# ASBB_GiantGecko.net
KiCad netlist of a schematic drawn in Altium Designer
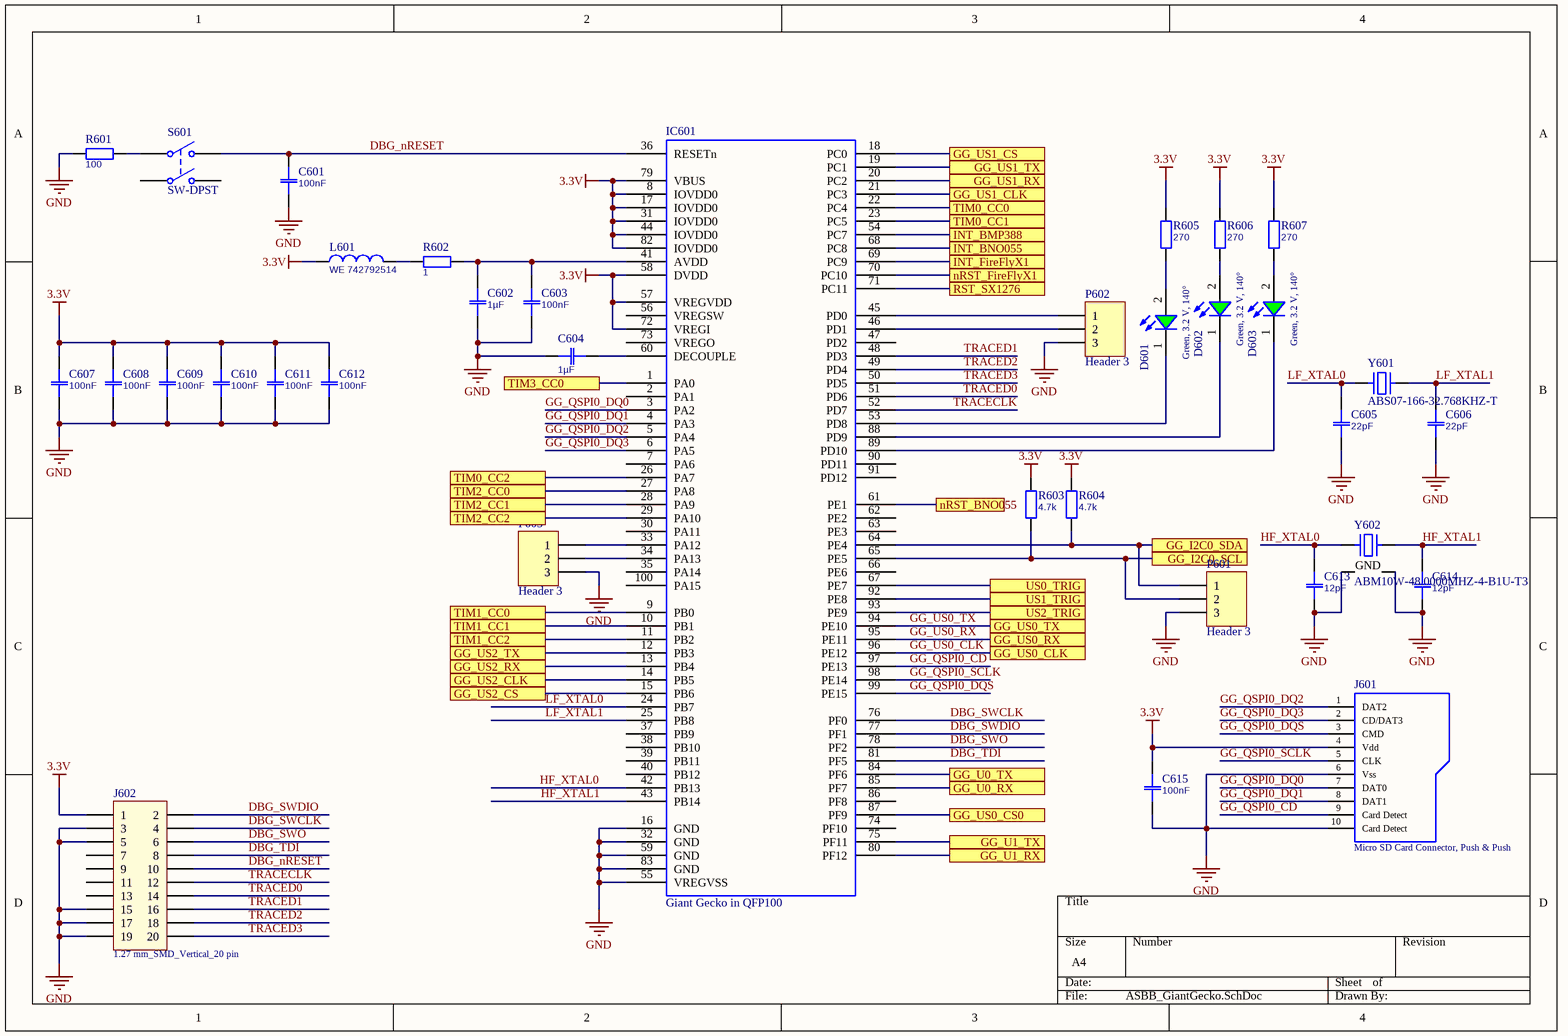
[diagram p0: ASBB_GiantGecko.SchDoc]

(export (version "E")
  (design (tool "Eeschema 10.0.6"))
  (components
    (comp (ref "C601")
      (value "100nF")
      (footprint "0603")
      (description "Capacitor")
      (fields (field (name "PARTNUMBER") "?"))
      (libsource (lib "FZI") (part "Capacitor"))
    )
    (comp (ref "C602")
      (value "1µF")
      (footprint "0603")
      (description "Capacitor")
      (fields (field (name "PARTNUMBER") "?"))
      (libsource (lib "FZI") (part "Capacitor"))
    )
    (comp (ref "C603")
      (value "100nF")
      (footprint "0603")
      (description "Capacitor")
      (fields (field (name "PARTNUMBER") "?"))
      (libsource (lib "FZI") (part "Capacitor"))
    )
    (comp (ref "C604")
      (value "1µF")
      (footprint "0603")
      (description "Capacitor")
      (fields (field (name "PARTNUMBER") "?"))
      (libsource (lib "FZI") (part "Capacitor"))
    )
    (comp (ref "C605")
      (value "22pF")
      (footprint "0603")
      (description "Capacitor")
      (fields (field (name "PARTNUMBER") "?"))
      (libsource (lib "FZI") (part "Capacitor"))
    )
    (comp (ref "C606")
      (value "22pF")
      (footprint "0603")
      (description "Capacitor")
      (fields (field (name "PARTNUMBER") "?"))
      (libsource (lib "FZI") (part "Capacitor"))
    )
    (comp (ref "C607")
      (value "100nF")
      (footprint "0603")
      (description "Capacitor")
      (fields (field (name "PARTNUMBER") "?"))
      (libsource (lib "FZI") (part "Capacitor"))
    )
    (comp (ref "C608")
      (value "100nF")
      (footprint "0603")
      (description "Capacitor")
      (fields (field (name "PARTNUMBER") "?"))
      (libsource (lib "FZI") (part "Capacitor"))
    )
    (comp (ref "C609")
      (value "100nF")
      (footprint "0603")
      (description "Capacitor")
      (fields (field (name "PARTNUMBER") "?"))
      (libsource (lib "FZI") (part "Capacitor"))
    )
    (comp (ref "C610")
      (value "100nF")
      (footprint "0603")
      (description "Capacitor")
      (fields (field (name "PARTNUMBER") "?"))
      (libsource (lib "FZI") (part "Capacitor"))
    )
    (comp (ref "C611")
      (value "100nF")
      (footprint "0603")
      (description "Capacitor")
      (fields (field (name "PARTNUMBER") "?"))
      (libsource (lib "FZI") (part "Capacitor"))
    )
    (comp (ref "C612")
      (value "100nF")
      (footprint "0603")
      (description "Capacitor")
      (fields (field (name "PARTNUMBER") "?"))
      (libsource (lib "FZI") (part "Capacitor"))
    )
    (comp (ref "C613")
      (value "12pF")
      (footprint "0603")
      (description "Capacitor")
      (fields (field (name "PARTNUMBER") "?"))
      (libsource (lib "FZI") (part "Capacitor"))
    )
    (comp (ref "C614")
      (value "12pF")
      (footprint "0603")
      (description "Capacitor")
      (fields (field (name "PARTNUMBER") "?"))
      (libsource (lib "FZI") (part "Capacitor"))
    )
    (comp (ref "C615")
      (value "100nF")
      (footprint "0603")
      (description "Capacitor")
      (fields (field (name "PARTNUMBER") "?"))
      (libsource (lib "FZI") (part "Capacitor"))
    )
    (comp (ref "D601")
      (value "Green, 3.2 V, 140°")
      (footprint "WL-SMCW_0603")
      (description "WL-SMCW SMD Mono-color Chip LED Waterclear, size 0603, Green, 3.2 V, 140°")
      (fields (field (name "PART NUMBER") "150060GS75000") (field (name "PUBLISHER") "Wurth Elektronik"))
      (libsource (lib "ALTIUM-WL-SMCW-rev18b") (part "150060GS75000"))
    )
    (comp (ref "D602")
      (value "Green, 3.2 V, 140°")
      (footprint "WL-SMCW_0603")
      (description "WL-SMCW SMD Mono-color Chip LED Waterclear, size 0603, Green, 3.2 V, 140°")
      (fields (field (name "PART NUMBER") "150060GS75000") (field (name "PUBLISHER") "Wurth Elektronik"))
      (libsource (lib "ALTIUM-WL-SMCW-rev18b") (part "150060GS75000"))
    )
    (comp (ref "D603")
      (value "Green, 3.2 V, 140°")
      (footprint "WL-SMCW_0603")
      (description "WL-SMCW SMD Mono-color Chip LED Waterclear, size 0603, Green, 3.2 V, 140°")
      (fields (field (name "PART NUMBER") "150060GS75000") (field (name "PUBLISHER") "Wurth Elektronik"))
      (libsource (lib "ALTIUM-WL-SMCW-rev18b") (part "150060GS75000"))
    )
    (comp (ref "IC601")
      (value "Giant Gecko in QFP100")
      (footprint "TQFP100")
      (libsource (lib "ASBB") (part "EFM32GG11B8xx"))
    )
    (comp (ref "J601")
      (value "Micro SD Card Connector, Push & Push")
      (footprint "693071010811")
      (description "WR-CRD Micro SD Card Connector, Push & Push, with card detection")
      (fields (field (name "PART NUMBER") "693071010811") (field (name "PUBLISHER") "Wurth Elektronik"))
      (libsource (lib "ALTIUM-WR-CRD-rev18a") (part "693071010811"))
    )
    (comp (ref "J602")
      (value "1.27 mm_SMD_Vertical_20 pin")
      (footprint "62102021021")
      (description "Pin Header WR-PHD, pitch 1.27 mm, SMD, Vertical, dual row, 20 pin")
      (fields (field (name "PART NUMBER") "62102021021") (field (name "PUBLISHER") "Wurth Elektronik"))
      (libsource (lib "6220xx21121 (rev18a)") (part "62102021021"))
    )
    (comp (ref "L601")
      (value "WE 742792514")
      (footprint "1812")
      (description "Inductor")
      (fields (field (name "PARTNUMBER") "?"))
      (libsource (lib "FZI") (part "Inductor"))
    )
    (comp (ref "P601")
      (value "Header 3")
      (footprint "HDR1X3")
      (description "Header, 3-Pin")
      (fields (field (name "PUBLISHER") "Altium Limited"))
      (libsource (lib "Miscellaneous Connectors") (part "Header 3"))
    )
    (comp (ref "P602")
      (value "Header 3")
      (footprint "HDR1X3")
      (description "Header, 3-Pin")
      (fields (field (name "PUBLISHER") "Altium Limited"))
      (libsource (lib "Miscellaneous Connectors") (part "Header 3"))
    )
    (comp (ref "P603")
      (value "Header 3")
      (footprint "HDR1X3")
      (description "Header, 3-Pin")
      (fields (field (name "PUBLISHER") "Altium Limited"))
      (libsource (lib "") (part "Header 3_1"))
    )
    (comp (ref "R601")
      (value "100")
      (footprint "0603")
      (description "Resistor")
      (fields (field (name "PARTNUMBER") "?"))
      (libsource (lib "FZI") (part "Resistor"))
    )
    (comp (ref "R602")
      (value "1")
      (footprint "0603")
      (description "Resistor")
      (fields (field (name "PARTNUMBER") "?"))
      (libsource (lib "FZI") (part "Resistor"))
    )
    (comp (ref "R603")
      (value "4.7k")
      (footprint "0603")
      (description "Resistor")
      (fields (field (name "PARTNUMBER") "?"))
      (libsource (lib "FZI") (part "Resistor"))
    )
    (comp (ref "R604")
      (value "4.7k")
      (footprint "0603")
      (description "Resistor")
      (fields (field (name "PARTNUMBER") "?"))
      (libsource (lib "FZI") (part "Resistor"))
    )
    (comp (ref "R605")
      (value "270")
      (footprint "0603")
      (description "Resistor")
      (fields (field (name "PARTNUMBER") "?"))
      (libsource (lib "FZI") (part "Resistor"))
    )
    (comp (ref "R606")
      (value "270")
      (footprint "0603")
      (description "Resistor")
      (fields (field (name "PARTNUMBER") "?"))
      (libsource (lib "FZI") (part "Resistor"))
    )
    (comp (ref "R607")
      (value "270")
      (footprint "0603")
      (description "Resistor")
      (fields (field (name "PARTNUMBER") "?"))
      (libsource (lib "FZI") (part "Resistor"))
    )
    (comp (ref "S601")
      (value "SW-DPST")
      (footprint "DPST-4")
      (description "Double-Pole, Single-Throw Switch")
      (fields (field (name "PUBLISHER") "Altium Limited"))
      (libsource (lib "Miscellaneous Devices") (part "SW-DPST"))
    )
    (comp (ref "Y601")
      (value "ABS07-166-32.768KHZ-T")
      (footprint "ABRACON ABS07")
      (description "SMT Crystal")
      (libsource (lib "Crystals") (part "Abracon Crystal ABS06"))
    )
    (comp (ref "Y602")
      (value "ABM10W-48.0000MHZ-4-B1U-T3")
      (footprint "ABRACON ABM10")
      (description "SMT Crystal")
      (libsource (lib "Crystals") (part "Abracon Crystal ABM10"))
    )
  )
  (nets
    (net (code "1") (name "/DBG_SWCLK") (class "Default")
      (node (ref "IC601") (pin "76") (pinfunction "PF0_76") (pintype "power_in"))
      (node (ref "J602") (pin "4") (pinfunction "4_4") (pintype "passive"))
    )
    (net (code "2") (name "/DBG_SWDIO") (class "Default")
      (node (ref "IC601") (pin "77") (pinfunction "PF1_77") (pintype "power_in"))
      (node (ref "J602") (pin "2") (pinfunction "2_2") (pintype "passive"))
    )
    (net (code "3") (name "/DBG_SWO") (class "Default")
      (node (ref "IC601") (pin "78") (pinfunction "PF2_78") (pintype "power_in"))
      (node (ref "J602") (pin "6") (pinfunction "6_6") (pintype "passive"))
    )
    (net (code "4") (name "/DBG_TDI") (class "Default")
      (node (ref "IC601") (pin "81") (pinfunction "PF5_81") (pintype "power_in"))
      (node (ref "J602") (pin "8") (pinfunction "8_8") (pintype "passive"))
    )
    (net (code "5") (name "/DBG_nRESET") (class "Default")
      (node (ref "C601") (pin "1") (pinfunction "1_1") (pintype "passive"))
      (node (ref "IC601") (pin "36") (pinfunction "RESETn_36") (pintype "power_in"))
      (node (ref "J602") (pin "10") (pinfunction "10_10") (pintype "passive"))
      (node (ref "S601") (pin "2") (pinfunction "NO1_2") (pintype "passive"))
    )
    (net (code "6") (name "/GG_I2C0_SCL") (class "Default")
      (node (ref "IC601") (pin "65") (pinfunction "PE5_65") (pintype "power_in"))
      (node (ref "P601") (pin "2") (pinfunction "2_2") (pintype "passive"))
      (node (ref "R603") (pin "1") (pinfunction "1_1") (pintype "passive"))
    )
    (net (code "7") (name "/GG_I2C0_SDA") (class "Default")
      (node (ref "IC601") (pin "64") (pinfunction "PE4_64") (pintype "power_in"))
      (node (ref "P601") (pin "1") (pinfunction "1_1") (pintype "passive"))
      (node (ref "R604") (pin "1") (pinfunction "1_1") (pintype "passive"))
    )
    (net (code "8") (name "/GG_QSPI0_CD") (class "Default")
      (node (ref "IC601") (pin "97") (pinfunction "PE13_97") (pintype "power_in"))
      (node (ref "J601") (pin "9") (pinfunction "Card_Detect_9") (pintype "passive"))
    )
    (net (code "9") (name "/GG_QSPI0_DQ0") (class "Default")
      (node (ref "IC601") (pin "3") (pinfunction "PA2_3") (pintype "power_in"))
      (node (ref "J601") (pin "7") (pinfunction "DAT0_7") (pintype "passive"))
    )
    (net (code "10") (name "/GG_QSPI0_DQ1") (class "Default")
      (node (ref "IC601") (pin "4") (pinfunction "PA3_4") (pintype "power_in"))
      (node (ref "J601") (pin "8") (pinfunction "DAT1_8") (pintype "passive"))
    )
    (net (code "11") (name "/GG_QSPI0_DQ2") (class "Default")
      (node (ref "IC601") (pin "5") (pinfunction "PA4_5") (pintype "power_in"))
      (node (ref "J601") (pin "1") (pinfunction "DAT2_1") (pintype "passive"))
    )
    (net (code "12") (name "/GG_QSPI0_DQ3") (class "Default")
      (node (ref "IC601") (pin "6") (pinfunction "PA5_6") (pintype "power_in"))
      (node (ref "J601") (pin "2") (pinfunction "CD/DAT3_2") (pintype "passive"))
    )
    (net (code "13") (name "/GG_QSPI0_DQS") (class "Default")
      (node (ref "IC601") (pin "99") (pinfunction "PE15_99") (pintype "power_in"))
      (node (ref "J601") (pin "3") (pinfunction "CMD_3") (pintype "passive"))
    )
    (net (code "14") (name "/GG_QSPI0_SCLK") (class "Default")
      (node (ref "IC601") (pin "98") (pinfunction "PE14_98") (pintype "power_in"))
      (node (ref "J601") (pin "5") (pinfunction "CLK_5") (pintype "passive"))
    )
    (net (code "15") (name "/GG_U0_RX") (class "Default")
      (node (ref "IC601") (pin "85") (pinfunction "PF7_85") (pintype "power_in"))
    )
    (net (code "16") (name "/GG_U0_TX") (class "Default")
      (node (ref "IC601") (pin "84") (pinfunction "PF6_84") (pintype "power_in"))
    )
    (net (code "17") (name "/GG_U1_RX") (class "Default")
      (node (ref "IC601") (pin "80") (pinfunction "PF12_80") (pintype "power_in"))
    )
    (net (code "18") (name "/GG_U1_TX") (class "Default")
      (node (ref "IC601") (pin "75") (pinfunction "PF11_75") (pintype "power_in"))
    )
    (net (code "19") (name "/GG_US0_CLK") (class "Default")
      (node (ref "IC601") (pin "96") (pinfunction "PE12_96") (pintype "power_in"))
    )
    (net (code "20") (name "/GG_US0_CS0") (class "Default")
      (node (ref "IC601") (pin "87") (pinfunction "PF9_87") (pintype "power_in"))
    )
    (net (code "21") (name "/GG_US0_RX") (class "Default")
      (node (ref "IC601") (pin "95") (pinfunction "PE11_95") (pintype "power_in"))
    )
    (net (code "22") (name "/GG_US0_TX") (class "Default")
      (node (ref "IC601") (pin "94") (pinfunction "PE10_94") (pintype "power_in"))
    )
    (net (code "23") (name "/GG_US1_CLK") (class "Default")
      (node (ref "IC601") (pin "21") (pinfunction "PC3_21") (pintype "power_in"))
    )
    (net (code "24") (name "/GG_US1_CS") (class "Default")
      (node (ref "IC601") (pin "18") (pinfunction "PC0_18") (pintype "power_in"))
    )
    (net (code "25") (name "/GG_US1_RX") (class "Default")
      (node (ref "IC601") (pin "20") (pinfunction "PC2_20") (pintype "power_in"))
    )
    (net (code "26") (name "/GG_US1_TX") (class "Default")
      (node (ref "IC601") (pin "19") (pinfunction "PC1_19") (pintype "power_in"))
    )
    (net (code "27") (name "/GG_US2_CLK") (class "Default")
      (node (ref "IC601") (pin "14") (pinfunction "PB5_14") (pintype "power_in"))
    )
    (net (code "28") (name "/GG_US2_CS") (class "Default")
      (node (ref "IC601") (pin "15") (pinfunction "PB6_15") (pintype "power_in"))
    )
    (net (code "29") (name "/GG_US2_RX") (class "Default")
      (node (ref "IC601") (pin "13") (pinfunction "PB4_13") (pintype "power_in"))
    )
    (net (code "30") (name "/GG_US2_TX") (class "Default")
      (node (ref "IC601") (pin "12") (pinfunction "PB3_12") (pintype "power_in"))
    )
    (net (code "31") (name "/HF_XTAL0") (class "Default")
      (node (ref "C613") (pin "1") (pinfunction "1_1") (pintype "passive"))
      (node (ref "IC601") (pin "42") (pinfunction "PB13_42") (pintype "power_in"))
      (node (ref "Y602") (pin "1") (pinfunction "1_1") (pintype "passive"))
    )
    (net (code "32") (name "/HF_XTAL1") (class "Default")
      (node (ref "C614") (pin "1") (pinfunction "1_1") (pintype "passive"))
      (node (ref "IC601") (pin "43") (pinfunction "PB14_43") (pintype "power_in"))
      (node (ref "Y602") (pin "3") (pinfunction "3_3") (pintype "passive"))
    )
    (net (code "33") (name "/INT_BMP388") (class "Default")
      (node (ref "IC601") (pin "54") (pinfunction "PC7_54") (pintype "power_in"))
    )
    (net (code "34") (name "/INT_BNO055") (class "Default")
      (node (ref "IC601") (pin "68") (pinfunction "PC8_68") (pintype "power_in"))
    )
    (net (code "35") (name "/INT_FireFlyX1") (class "Default")
      (node (ref "IC601") (pin "69") (pinfunction "PC9_69") (pintype "power_in"))
    )
    (net (code "36") (name "/LF_XTAL0") (class "Default")
      (node (ref "C605") (pin "1") (pinfunction "1_1") (pintype "passive"))
      (node (ref "IC601") (pin "24") (pinfunction "PB7_24") (pintype "power_in"))
      (node (ref "Y601") (pin "1") (pinfunction "1_1") (pintype "passive"))
    )
    (net (code "37") (name "/LF_XTAL1") (class "Default")
      (node (ref "C606") (pin "1") (pinfunction "1_1") (pintype "passive"))
      (node (ref "IC601") (pin "25") (pinfunction "PB8_25") (pintype "power_in"))
      (node (ref "Y601") (pin "2") (pinfunction "2_2") (pintype "passive"))
    )
    (net (code "38") (name "/RST_SX1276") (class "Default")
      (node (ref "IC601") (pin "71") (pinfunction "PC11_71") (pintype "power_in"))
    )
    (net (code "39") (name "/TIM0_CC0") (class "Default")
      (node (ref "IC601") (pin "22") (pinfunction "PC4_22") (pintype "power_in"))
    )
    (net (code "40") (name "/TIM0_CC1") (class "Default")
      (node (ref "IC601") (pin "23") (pinfunction "PC5_23") (pintype "power_in"))
    )
    (net (code "41") (name "/TIM0_CC2") (class "Default")
      (node (ref "IC601") (pin "26") (pinfunction "PA7_26") (pintype "power_in"))
    )
    (net (code "42") (name "/TIM1_CC0") (class "Default")
      (node (ref "IC601") (pin "9") (pinfunction "PB0_9") (pintype "power_in"))
    )
    (net (code "43") (name "/TIM1_CC1") (class "Default")
      (node (ref "IC601") (pin "10") (pinfunction "PB1_10") (pintype "power_in"))
    )
    (net (code "44") (name "/TIM1_CC2") (class "Default")
      (node (ref "IC601") (pin "11") (pinfunction "PB2_11") (pintype "power_in"))
    )
    (net (code "45") (name "/TIM2_CC0") (class "Default")
      (node (ref "IC601") (pin "27") (pinfunction "PA8_27") (pintype "power_in"))
    )
    (net (code "46") (name "/TIM2_CC1") (class "Default")
      (node (ref "IC601") (pin "28") (pinfunction "PA9_28") (pintype "power_in"))
    )
    (net (code "47") (name "/TIM2_CC2") (class "Default")
      (node (ref "IC601") (pin "29") (pinfunction "PA10_29") (pintype "power_in"))
    )
    (net (code "48") (name "/TIM3_CC0") (class "Default")
      (node (ref "IC601") (pin "1") (pinfunction "PA0_1") (pintype "power_in"))
    )
    (net (code "49") (name "/TRACECLK") (class "Default")
      (node (ref "IC601") (pin "52") (pinfunction "PD7_52") (pintype "power_in"))
      (node (ref "J602") (pin "12") (pinfunction "12_12") (pintype "passive"))
    )
    (net (code "50") (name "/TRACED0") (class "Default")
      (node (ref "IC601") (pin "51") (pinfunction "PD6_51") (pintype "power_in"))
      (node (ref "J602") (pin "14") (pinfunction "14_14") (pintype "passive"))
    )
    (net (code "51") (name "/TRACED1") (class "Default")
      (node (ref "IC601") (pin "48") (pinfunction "PD3_48") (pintype "power_in"))
      (node (ref "J602") (pin "16") (pinfunction "16_16") (pintype "passive"))
    )
    (net (code "52") (name "/TRACED2") (class "Default")
      (node (ref "IC601") (pin "49") (pinfunction "PD4_49") (pintype "power_in"))
      (node (ref "J602") (pin "18") (pinfunction "18_18") (pintype "passive"))
    )
    (net (code "53") (name "/TRACED3") (class "Default")
      (node (ref "IC601") (pin "50") (pinfunction "PD5_50") (pintype "power_in"))
      (node (ref "J602") (pin "20") (pinfunction "20_20") (pintype "passive"))
    )
    (net (code "54") (name "/US0_TRIG") (class "Default")
      (node (ref "IC601") (pin "67") (pinfunction "PE7_67") (pintype "power_in"))
    )
    (net (code "55") (name "/US1_TRIG") (class "Default")
      (node (ref "IC601") (pin "92") (pinfunction "PE8_92") (pintype "power_in"))
    )
    (net (code "56") (name "/US2_TRIG") (class "Default")
      (node (ref "IC601") (pin "93") (pinfunction "PE9_93") (pintype "power_in"))
    )
    (net (code "57") (name "/nRST_BNO055") (class "Default")
      (node (ref "IC601") (pin "61") (pinfunction "PE1_61") (pintype "power_in"))
    )
    (net (code "58") (name "/nRST_FireFlyX1") (class "Default")
      (node (ref "IC601") (pin "70") (pinfunction "PC10_70") (pintype "power_in"))
    )
    (net (code "59") (name "3.3V") (class "Default")
      (node (ref "C607") (pin "1") (pinfunction "1_1") (pintype "passive"))
      (node (ref "C608") (pin "1") (pinfunction "1_1") (pintype "passive"))
      (node (ref "C609") (pin "1") (pinfunction "1_1") (pintype "passive"))
      (node (ref "C610") (pin "1") (pinfunction "1_1") (pintype "passive"))
      (node (ref "C611") (pin "1") (pinfunction "1_1") (pintype "passive"))
      (node (ref "C612") (pin "1") (pinfunction "1_1") (pintype "passive"))
      (node (ref "C615") (pin "1") (pinfunction "1_1") (pintype "passive"))
      (node (ref "IC601") (pin "17") (pinfunction "IOVDD0_17") (pintype "power_in"))
      (node (ref "IC601") (pin "31") (pinfunction "IOVDD0_31") (pintype "power_in"))
      (node (ref "IC601") (pin "44") (pinfunction "IOVDD0_44") (pintype "power_in"))
      (node (ref "IC601") (pin "57") (pinfunction "VREGVDD_57") (pintype "power_in"))
      (node (ref "IC601") (pin "58") (pinfunction "DVDD_58") (pintype "power_in"))
      (node (ref "IC601") (pin "72") (pinfunction "VREGI_72") (pintype "power_in"))
      (node (ref "IC601") (pin "79") (pinfunction "VBUS_79") (pintype "power_in"))
      (node (ref "IC601") (pin "8") (pinfunction "IOVDD0_8") (pintype "power_in"))
      (node (ref "IC601") (pin "82") (pinfunction "IOVDD0_82") (pintype "power_in"))
      (node (ref "J601") (pin "4") (pinfunction "Vdd_4") (pintype "passive"))
      (node (ref "J602") (pin "1") (pinfunction "1_1") (pintype "passive"))
      (node (ref "L601") (pin "1") (pinfunction "1_1") (pintype "passive"))
      (node (ref "R603") (pin "2") (pinfunction "2_2") (pintype "passive"))
      (node (ref "R604") (pin "2") (pinfunction "2_2") (pintype "passive"))
      (node (ref "R605") (pin "2") (pinfunction "2_2") (pintype "passive"))
      (node (ref "R606") (pin "2") (pinfunction "2_2") (pintype "passive"))
      (node (ref "R607") (pin "2") (pinfunction "2_2") (pintype "passive"))
    )
    (net (code "60") (name "GND") (class "Default")
      (node (ref "C601") (pin "2") (pinfunction "2_2") (pintype "passive"))
      (node (ref "C602") (pin "2") (pinfunction "2_2") (pintype "passive"))
      (node (ref "C603") (pin "2") (pinfunction "2_2") (pintype "passive"))
      (node (ref "C604") (pin "1") (pinfunction "1_1") (pintype "passive"))
      (node (ref "C605") (pin "2") (pinfunction "2_2") (pintype "passive"))
      (node (ref "C606") (pin "2") (pinfunction "2_2") (pintype "passive"))
      (node (ref "C607") (pin "2") (pinfunction "2_2") (pintype "passive"))
      (node (ref "C608") (pin "2") (pinfunction "2_2") (pintype "passive"))
      (node (ref "C609") (pin "2") (pinfunction "2_2") (pintype "passive"))
      (node (ref "C610") (pin "2") (pinfunction "2_2") (pintype "passive"))
      (node (ref "C611") (pin "2") (pinfunction "2_2") (pintype "passive"))
      (node (ref "C612") (pin "2") (pinfunction "2_2") (pintype "passive"))
      (node (ref "C613") (pin "2") (pinfunction "2_2") (pintype "passive"))
      (node (ref "C614") (pin "2") (pinfunction "2_2") (pintype "passive"))
      (node (ref "C615") (pin "2") (pinfunction "2_2") (pintype "passive"))
      (node (ref "IC601") (pin "16") (pinfunction "GND_16") (pintype "power_in"))
      (node (ref "IC601") (pin "32") (pinfunction "GND_32") (pintype "power_in"))
      (node (ref "IC601") (pin "55") (pinfunction "VREGVSS_55") (pintype "power_in"))
      (node (ref "IC601") (pin "59") (pinfunction "GND_59") (pintype "power_in"))
      (node (ref "IC601") (pin "83") (pinfunction "GND_83") (pintype "power_in"))
      (node (ref "J601") (pin "10") (pinfunction "Card_Detect_10") (pintype "passive"))
      (node (ref "J601") (pin "6") (pinfunction "Vss_6") (pintype "passive"))
      (node (ref "J602") (pin "15") (pinfunction "15_15") (pintype "passive"))
      (node (ref "J602") (pin "17") (pinfunction "17_17") (pintype "passive"))
      (node (ref "J602") (pin "19") (pinfunction "19_19") (pintype "passive"))
      (node (ref "J602") (pin "3") (pinfunction "3_3") (pintype "passive"))
      (node (ref "J602") (pin "5") (pinfunction "5_5") (pintype "passive"))
      (node (ref "P601") (pin "3") (pinfunction "3_3") (pintype "passive"))
      (node (ref "P602") (pin "3") (pinfunction "3_3") (pintype "passive"))
      (node (ref "P603") (pin "3") (pinfunction "3_3") (pintype "passive"))
      (node (ref "R601") (pin "1") (pinfunction "1_1") (pintype "passive"))
      (node (ref "Y602") (pin "2") (pinfunction "GND_2") (pintype "passive"))
      (node (ref "Y602") (pin "4") (pinfunction "GND_4") (pintype "passive"))
    )
    (net (code "61") (name "Net-(D601-A)") (class "Default")
      (node (ref "D601") (pin "2") (pinfunction "A_2") (pintype "passive"))
      (node (ref "R605") (pin "1") (pinfunction "1_1") (pintype "passive"))
    )
    (net (code "62") (name "Net-(D601-K)") (class "Default")
      (node (ref "D601") (pin "1") (pinfunction "K_1") (pintype "passive"))
      (node (ref "IC601") (pin "53") (pinfunction "PD8_53") (pintype "power_in"))
    )
    (net (code "63") (name "Net-(D602-A)") (class "Default")
      (node (ref "D602") (pin "2") (pinfunction "A_2") (pintype "passive"))
      (node (ref "R606") (pin "1") (pinfunction "1_1") (pintype "passive"))
    )
    (net (code "64") (name "Net-(D602-K)") (class "Default")
      (node (ref "D602") (pin "1") (pinfunction "K_1") (pintype "passive"))
      (node (ref "IC601") (pin "88") (pinfunction "PD9_88") (pintype "power_in"))
    )
    (net (code "65") (name "Net-(D603-A)") (class "Default")
      (node (ref "D603") (pin "2") (pinfunction "A_2") (pintype "passive"))
      (node (ref "R607") (pin "1") (pinfunction "1_1") (pintype "passive"))
    )
    (net (code "66") (name "Net-(D603-K)") (class "Default")
      (node (ref "D603") (pin "1") (pinfunction "K_1") (pintype "passive"))
      (node (ref "IC601") (pin "89") (pinfunction "PD10_89") (pintype "power_in"))
    )
    (net (code "67") (name "Net-(IC601-AVDD)") (class "Default")
      (node (ref "C602") (pin "1") (pinfunction "1_1") (pintype "passive"))
      (node (ref "C603") (pin "1") (pinfunction "1_1") (pintype "passive"))
      (node (ref "IC601") (pin "41") (pinfunction "AVDD_41") (pintype "power_in"))
      (node (ref "R602") (pin "2") (pinfunction "2_2") (pintype "passive"))
    )
    (net (code "68") (name "Net-(IC601-DECOUPLE)") (class "Default")
      (node (ref "C604") (pin "2") (pinfunction "2_2") (pintype "passive"))
      (node (ref "IC601") (pin "60") (pinfunction "DECOUPLE_60") (pintype "power_in"))
    )
    (net (code "69") (name "Net-(IC601-PA12)") (class "Default")
      (node (ref "IC601") (pin "33") (pinfunction "PA12_33") (pintype "power_in"))
      (node (ref "P603") (pin "1") (pinfunction "1_1") (pintype "passive"))
    )
    (net (code "70") (name "Net-(IC601-PA13)") (class "Default")
      (node (ref "IC601") (pin "34") (pinfunction "PA13_34") (pintype "power_in"))
      (node (ref "P603") (pin "2") (pinfunction "2_2") (pintype "passive"))
    )
    (net (code "71") (name "Net-(IC601-PD0)") (class "Default")
      (node (ref "IC601") (pin "45") (pinfunction "PD0_45") (pintype "power_in"))
      (node (ref "P602") (pin "1") (pinfunction "1_1") (pintype "passive"))
    )
    (net (code "72") (name "Net-(IC601-PD1)") (class "Default")
      (node (ref "IC601") (pin "46") (pinfunction "PD1_46") (pintype "power_in"))
      (node (ref "P602") (pin "2") (pinfunction "2_2") (pintype "passive"))
    )
    (net (code "73") (name "Net-(L601-Pad2)") (class "Default")
      (node (ref "L601") (pin "2") (pinfunction "2_2") (pintype "passive"))
      (node (ref "R602") (pin "1") (pinfunction "1_1") (pintype "passive"))
    )
    (net (code "74") (name "Net-(S601-COMMON1)") (class "Default")
      (node (ref "R601") (pin "2") (pinfunction "2_2") (pintype "passive"))
      (node (ref "S601") (pin "1") (pinfunction "COMMON1_1") (pintype "passive"))
    )
    (net (code "75") (name "unconnected-(IC601-PA1-Pad2)") (class "Default")
      (node (ref "IC601") (pin "2") (pinfunction "PA1_2") (pintype "power_in"))
    )
    (net (code "76") (name "unconnected-(IC601-PA6-Pad7)") (class "Default")
      (node (ref "IC601") (pin "7") (pinfunction "PA6_7") (pintype "power_in"))
    )
    (net (code "77") (name "unconnected-(IC601-PA11-Pad30)") (class "Default")
      (node (ref "IC601") (pin "30") (pinfunction "PA11_30") (pintype "power_in"))
    )
    (net (code "78") (name "unconnected-(IC601-PA14-Pad35)") (class "Default")
      (node (ref "IC601") (pin "35") (pinfunction "PA14_35") (pintype "power_in"))
    )
    (net (code "79") (name "unconnected-(IC601-PA15-Pad100)") (class "Default")
      (node (ref "IC601") (pin "100") (pinfunction "PA15_100") (pintype "power_in"))
    )
    (net (code "80") (name "unconnected-(IC601-PB9-Pad37)") (class "Default")
      (node (ref "IC601") (pin "37") (pinfunction "PB9_37") (pintype "power_in"))
    )
    (net (code "81") (name "unconnected-(IC601-PB10-Pad38)") (class "Default")
      (node (ref "IC601") (pin "38") (pinfunction "PB10_38") (pintype "power_in"))
    )
    (net (code "82") (name "unconnected-(IC601-PB11-Pad39)") (class "Default")
      (node (ref "IC601") (pin "39") (pinfunction "PB11_39") (pintype "power_in"))
    )
    (net (code "83") (name "unconnected-(IC601-PB12-Pad40)") (class "Default")
      (node (ref "IC601") (pin "40") (pinfunction "PB12_40") (pintype "power_in"))
    )
    (net (code "84") (name "unconnected-(IC601-PD2-Pad47)") (class "Default")
      (node (ref "IC601") (pin "47") (pinfunction "PD2_47") (pintype "power_in"))
    )
    (net (code "85") (name "unconnected-(IC601-PD11-Pad90)") (class "Default")
      (node (ref "IC601") (pin "90") (pinfunction "PD11_90") (pintype "power_in"))
    )
    (net (code "86") (name "unconnected-(IC601-PD12-Pad91)") (class "Default")
      (node (ref "IC601") (pin "91") (pinfunction "PD12_91") (pintype "power_in"))
    )
    (net (code "87") (name "unconnected-(IC601-PE2-Pad62)") (class "Default")
      (node (ref "IC601") (pin "62") (pinfunction "PE2_62") (pintype "power_in"))
    )
    (net (code "88") (name "unconnected-(IC601-PE3-Pad63)") (class "Default")
      (node (ref "IC601") (pin "63") (pinfunction "PE3_63") (pintype "power_in"))
    )
    (net (code "89") (name "unconnected-(IC601-PE6-Pad66)") (class "Default")
      (node (ref "IC601") (pin "66") (pinfunction "PE6_66") (pintype "power_in"))
    )
    (net (code "90") (name "unconnected-(IC601-PF8-Pad86)") (class "Default")
      (node (ref "IC601") (pin "86") (pinfunction "PF8_86") (pintype "power_in"))
    )
    (net (code "91") (name "unconnected-(IC601-PF10-Pad74)") (class "Default")
      (node (ref "IC601") (pin "74") (pinfunction "PF10_74") (pintype "power_in"))
    )
    (net (code "92") (name "unconnected-(IC601-VREGO-Pad73)") (class "Default")
      (node (ref "IC601") (pin "73") (pinfunction "VREGO_73") (pintype "power_in"))
    )
    (net (code "93") (name "unconnected-(IC601-VREGSW-Pad56)") (class "Default")
      (node (ref "IC601") (pin "56") (pinfunction "VREGSW_56") (pintype "power_in"))
    )
    (net (code "94") (name "unconnected-(J602-Pad7)") (class "Default")
      (node (ref "J602") (pin "7") (pinfunction "7_7") (pintype "passive"))
    )
    (net (code "95") (name "unconnected-(J602-Pad9)") (class "Default")
      (node (ref "J602") (pin "9") (pinfunction "9_9") (pintype "passive"))
    )
    (net (code "96") (name "unconnected-(J602-Pad11)") (class "Default")
      (node (ref "J602") (pin "11") (pinfunction "11_11") (pintype "passive"))
    )
    (net (code "97") (name "unconnected-(J602-Pad13)") (class "Default")
      (node (ref "J602") (pin "13") (pinfunction "13_13") (pintype "passive"))
    )
    (net (code "98") (name "unconnected-(S601-COMMON2-Pad3)") (class "Default")
      (node (ref "S601") (pin "3") (pinfunction "COMMON2_3") (pintype "passive"))
    )
    (net (code "99") (name "unconnected-(S601-NO2-Pad4)") (class "Default")
      (node (ref "S601") (pin "4") (pinfunction "NO2_4") (pintype "passive"))
    )
  )
)
